# design.net
KiCad netlist of a schematic drawn in Altium Designer
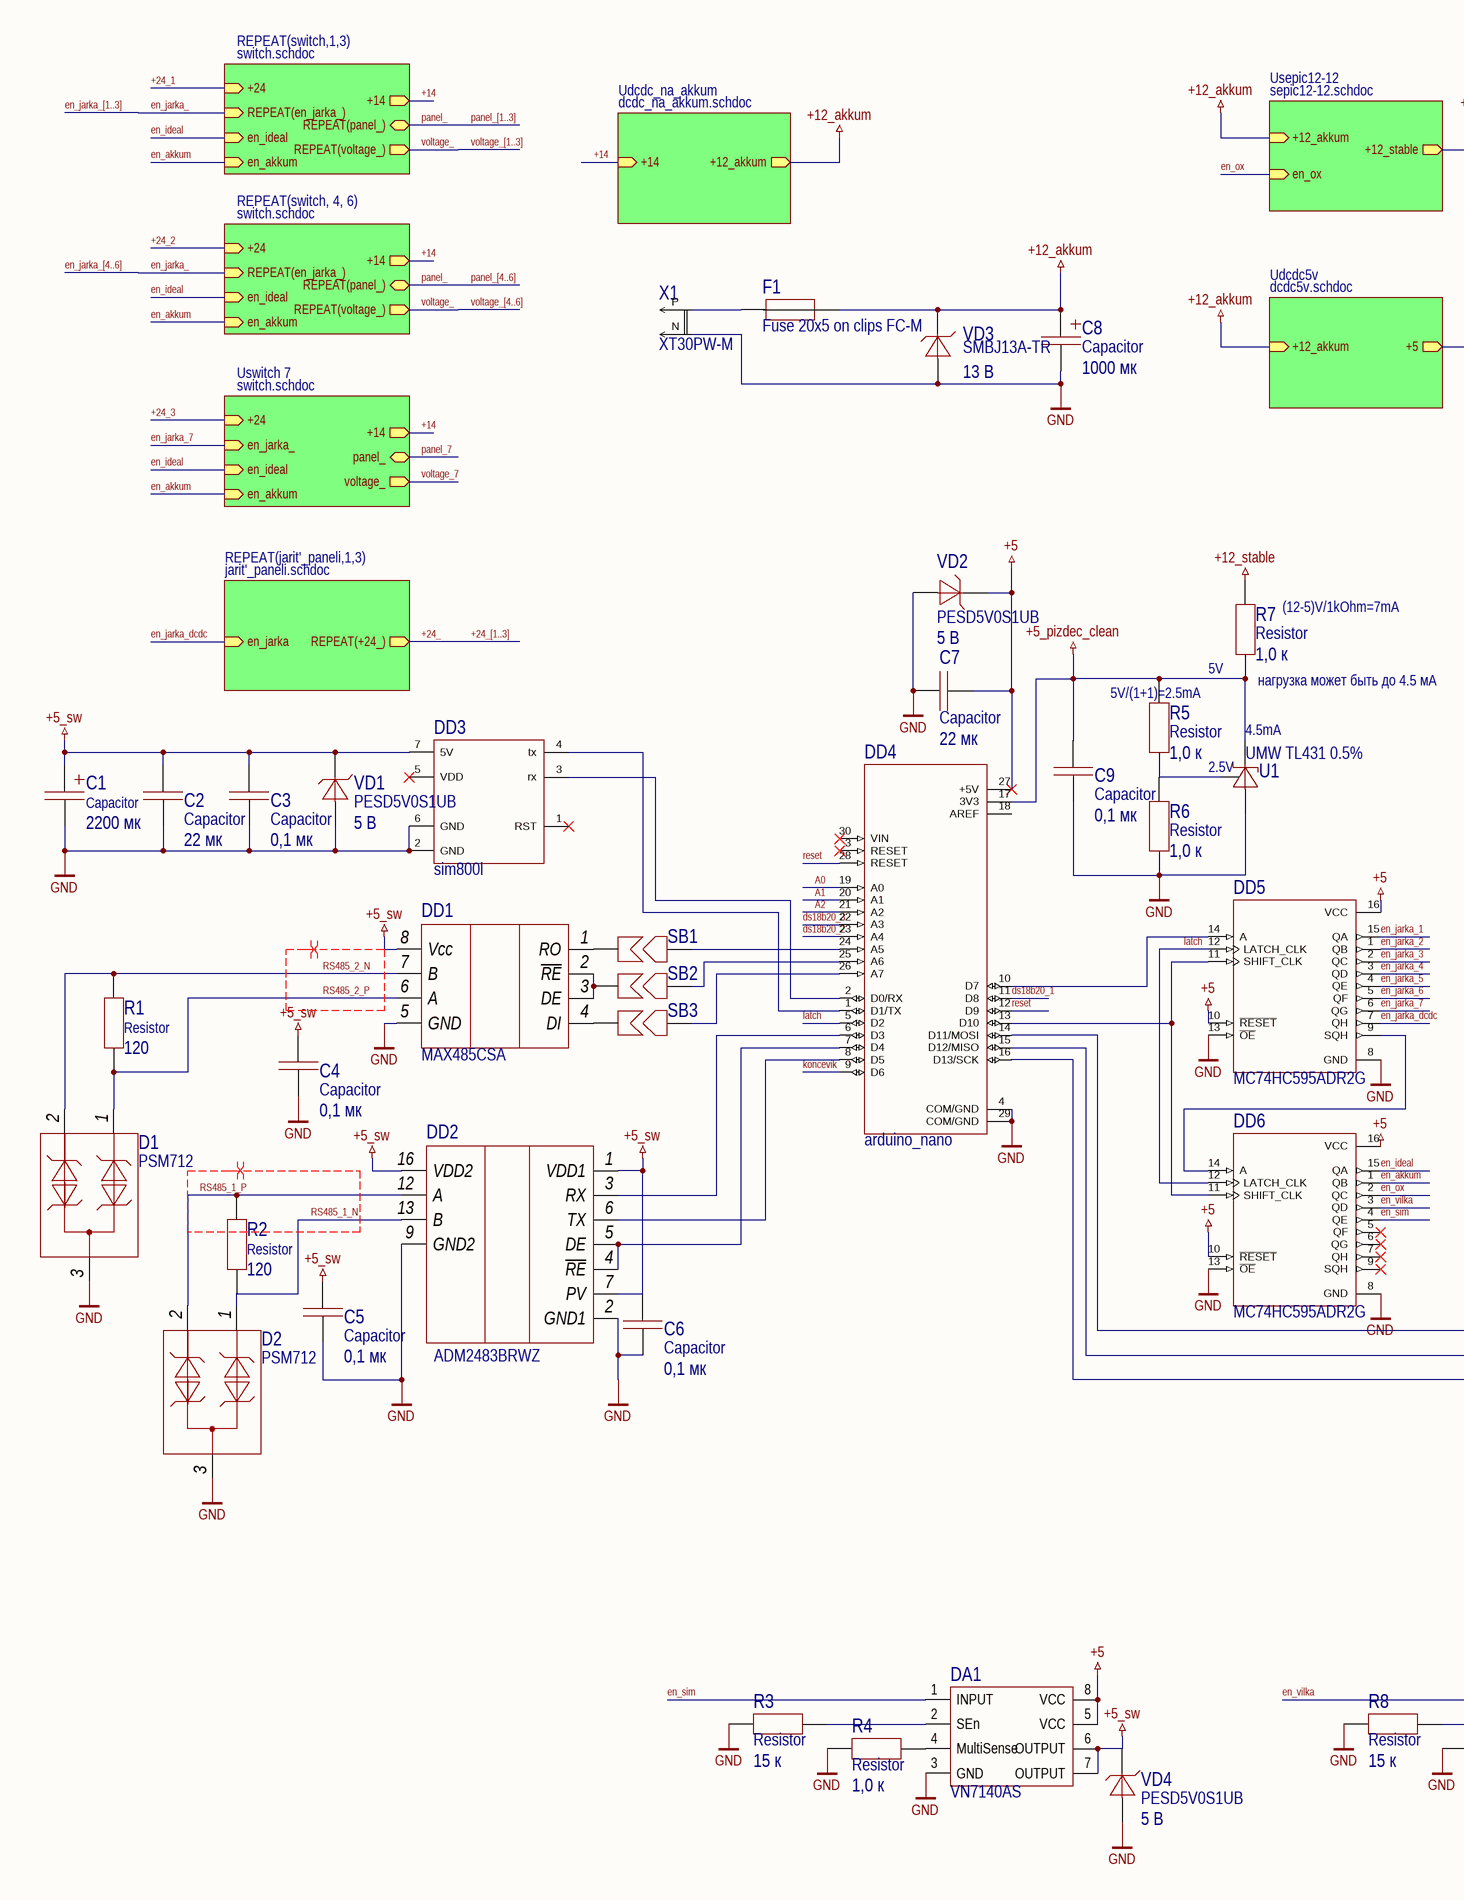
[diagram p0: хехема.SchDoc, left]
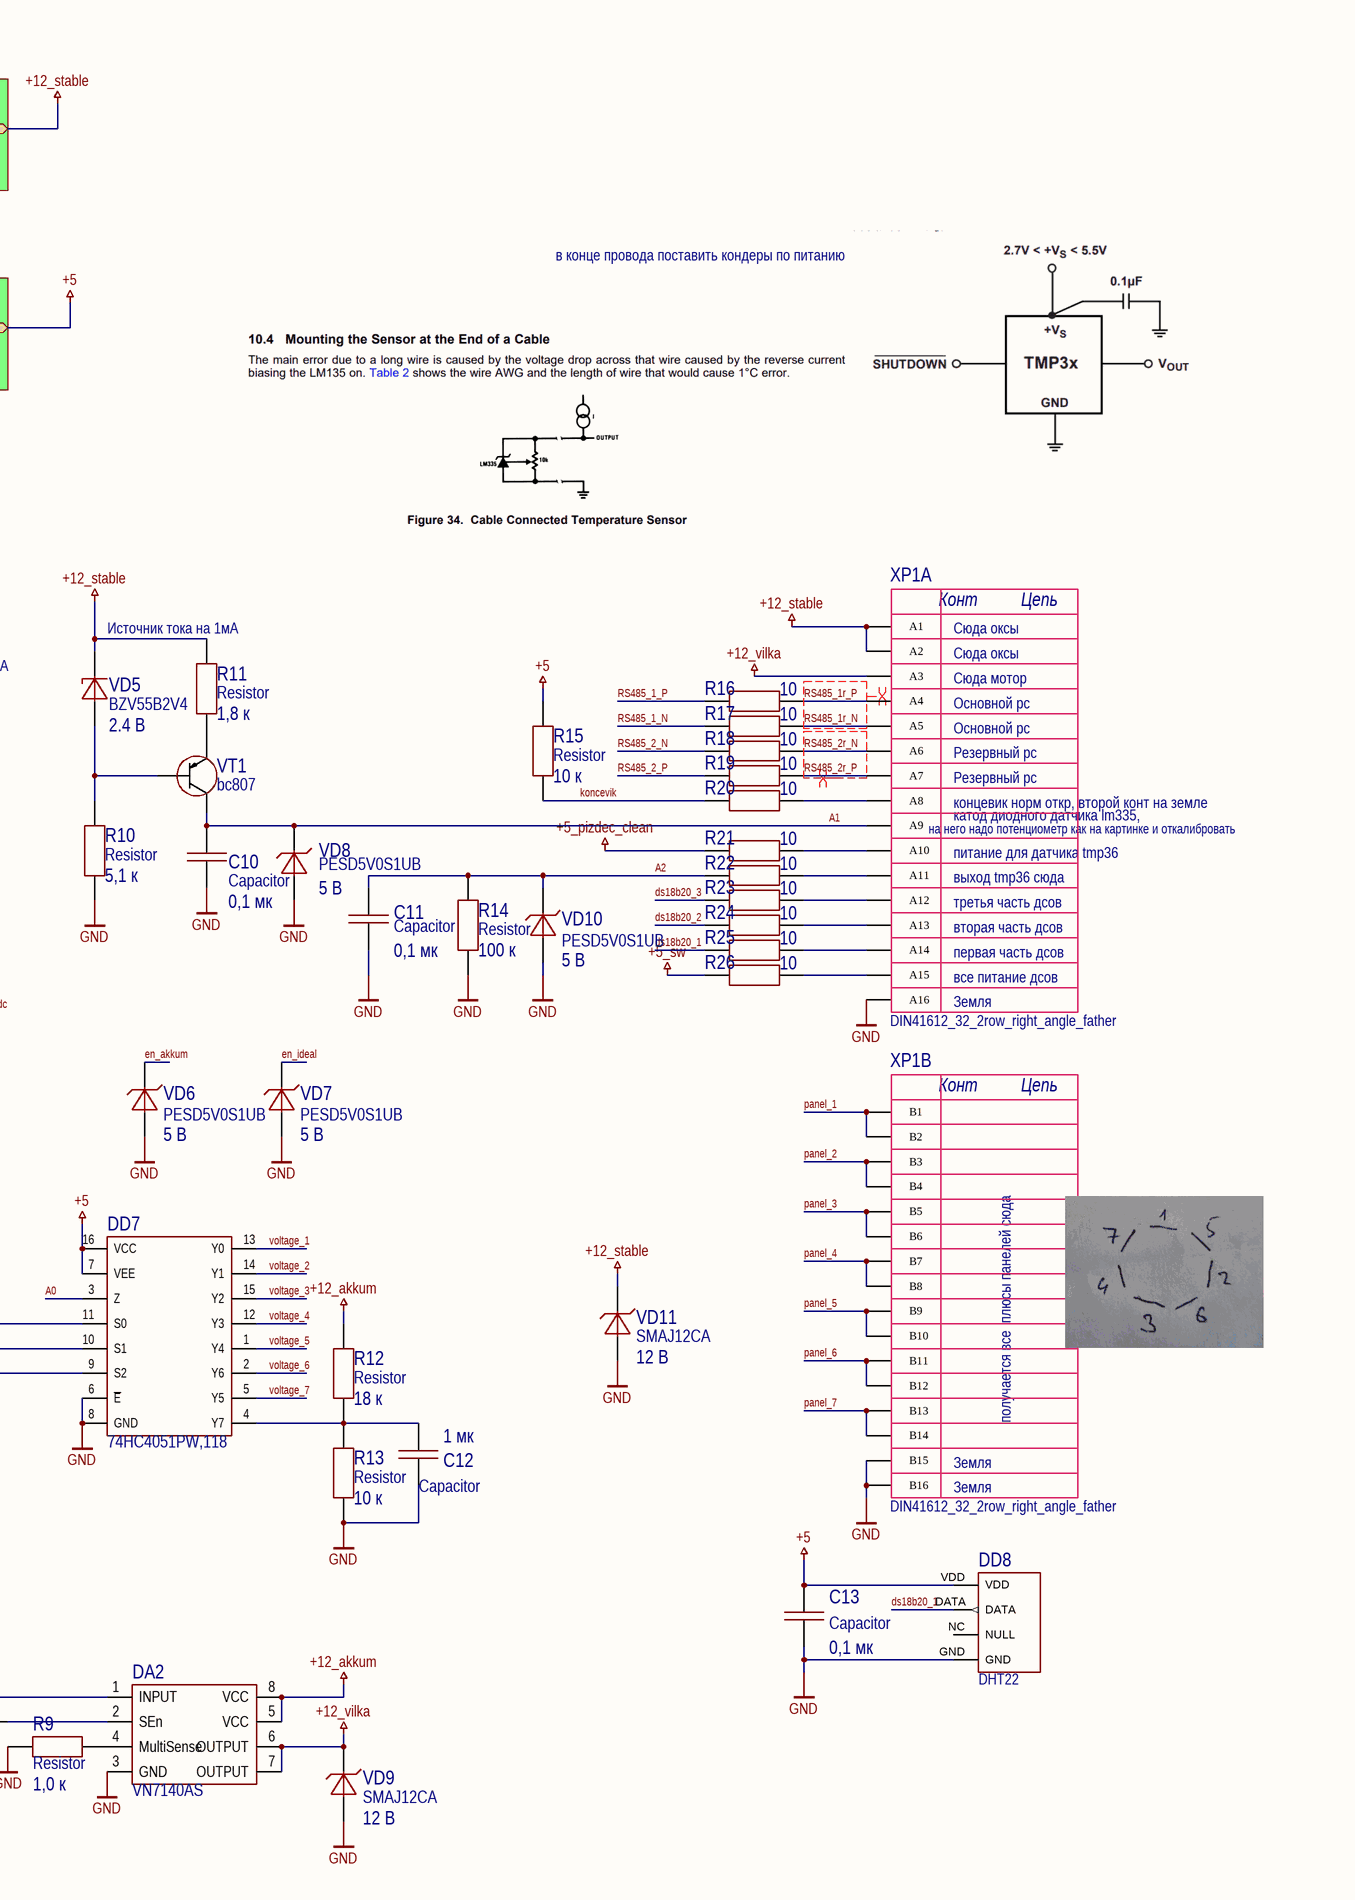
[diagram p1: хехема.SchDoc, right]

(export (version "E")
  (design (tool "Eeschema 10.0.6"))
  (components
    (comp (ref "C1")
      (value "Capacitor")
      (footprint "10x20_radial")
      (description "Конденсатор радиальный 2200мкФ 10В ±20% 10*19")
      (fields
        (field (name "ALTIUM_VALUE") "2200 мк")
        (field (name "PART NUMBER") "Capacitor_2200u_10V_10x20")
        (field (name "TOLERANCE") "20")
      )
      (libsource (lib "Hydrolib") (part "Capacitor_polar"))
    )
    (comp (ref "C2")
      (value "Capacitor")
      (footprint "1210C")
      (description "Конденсатор")
      (fields
        (field (name "ALTIUM_VALUE") "22 мк")
        (field (name "PART NUMBER") "Capacitor_22u_10_25V_X7R_1210C")
        (field (name "TOLERANCE") "0,1")
      )
      (libsource (lib "Hydrolib") (part "Capacitor"))
    )
    (comp (ref "C3")
      (value "Capacitor")
      (footprint "0603C")
      (description "Конденсатор")
      (fields
        (field (name "ALTIUM_VALUE") "0,1 мк")
        (field (name "PART NUMBER") "Capacitor_0,1u_10_50V_X7R_0603C")
        (field (name "TOLERANCE") "0,1")
      )
      (libsource (lib "Hydrolib") (part "Capacitor"))
    )
    (comp (ref "C4")
      (value "Capacitor")
      (footprint "0603C")
      (description "Конденсатор")
      (fields
        (field (name "ALTIUM_VALUE") "0,1 мк")
        (field (name "PART NUMBER") "Capacitor_0,1u_10_50V_X7R_0603C")
        (field (name "TOLERANCE") "0,1")
      )
      (libsource (lib "Hydrolib") (part "Capacitor"))
    )
    (comp (ref "C5")
      (value "Capacitor")
      (footprint "0603C")
      (description "Конденсатор")
      (fields
        (field (name "ALTIUM_VALUE") "0,1 мк")
        (field (name "PART NUMBER") "Capacitor_0,1u_10_50V_X7R_0603C")
        (field (name "TOLERANCE") "0,1")
      )
      (libsource (lib "Hydrolib") (part "Capacitor"))
    )
    (comp (ref "C6")
      (value "Capacitor")
      (footprint "0603C")
      (description "Конденсатор")
      (fields
        (field (name "ALTIUM_VALUE") "0,1 мк")
        (field (name "PART NUMBER") "Capacitor_0,1u_10_50V_X7R_0603C")
        (field (name "TOLERANCE") "0,1")
      )
      (libsource (lib "Hydrolib") (part "Capacitor"))
    )
    (comp (ref "C7")
      (value "Capacitor")
      (footprint "1210C")
      (description "Конденсатор")
      (fields
        (field (name "ALTIUM_VALUE") "22 мк")
        (field (name "PART NUMBER") "Capacitor_22u_10_25V_X7R_1210C")
        (field (name "TOLERANCE") "0,1")
      )
      (libsource (lib "Hydrolib") (part "Capacitor"))
    )
    (comp (ref "C8")
      (value "Capacitor")
      (footprint "SMD_cap_12,5x13,5")
      (description "Конденсатор алюминиевый электролитический 1000мкФ 25В 20% Low ESR 1100мА SMD12.5x13.5мм")
      (fields
        (field (name "ALTIUM_VALUE") "1000 мк")
        (field (name "PART NUMBER") "EEVFK1E102Q")
        (field (name "TOLERANCE") "20")
      )
      (libsource (lib "Hydrolib") (part "Capacitor_polar"))
    )
    (comp (ref "C9")
      (value "Capacitor")
      (footprint "0603C")
      (description "Конденсатор")
      (fields
        (field (name "ALTIUM_VALUE") "0,1 мк")
        (field (name "PART NUMBER") "Capacitor_0,1u_10_50V_X7R_0603C")
        (field (name "TOLERANCE") "0,1")
      )
      (libsource (lib "Hydrolib") (part "Capacitor"))
    )
    (comp (ref "C10")
      (value "Capacitor")
      (footprint "0603C")
      (description "Конденсатор")
      (fields
        (field (name "ALTIUM_VALUE") "0,1 мк")
        (field (name "PART NUMBER") "Capacitor_0,1u_10_50V_X7R_0603C")
        (field (name "TOLERANCE") "0,1")
      )
      (libsource (lib "Hydrolib") (part "Capacitor"))
    )
    (comp (ref "C11")
      (value "Capacitor")
      (footprint "0603C")
      (description "Конденсатор")
      (fields
        (field (name "ALTIUM_VALUE") "0,1 мк")
        (field (name "PART NUMBER") "Capacitor_0,1u_10_50V_X7R_0603C")
        (field (name "TOLERANCE") "0,1")
      )
      (libsource (lib "Hydrolib") (part "Capacitor"))
    )
    (comp (ref "C12")
      (value "Capacitor")
      (footprint "0603C")
      (description "Конденсатор")
      (fields
        (field (name "ALTIUM_VALUE") "1 мк")
        (field (name "PART NUMBER") "Capacitor_1u_10_50V_X7R_0603C")
        (field (name "TOLERANCE") "0,1")
      )
      (libsource (lib "Hydrolib") (part "Capacitor"))
    )
    (comp (ref "C13")
      (value "Capacitor")
      (footprint "0603C")
      (description "Конденсатор")
      (fields
        (field (name "ALTIUM_VALUE") "0,1 мк")
        (field (name "PART NUMBER") "Capacitor_0,1u_10_50V_X7R_0603C")
        (field (name "TOLERANCE") "0,1")
      )
      (libsource (lib "Hydrolib") (part "Capacitor"))
    )
    (comp (ref "D1")
      (value "PSM712")
      (footprint "SOT23-3")
      (description "Защитный диод для линии RS-485")
      (libsource (lib "Hydrolib") (part "TVS_2_2dir"))
    )
    (comp (ref "D2")
      (value "PSM712")
      (footprint "SOT23-3")
      (description "Защитный диод для линии RS-485")
      (libsource (lib "Hydrolib") (part "TVS_2_2dir"))
    )
    (comp (ref "DA1")
      (value "VN7140AS")
      (footprint "SOP8")
      (description "Силовой ключ верхнего плеча с аналоговой обратной связью MultiSense автомобильного применения")
      (libsource (lib "Hydrolib") (part "VN7140AS"))
    )
    (comp (ref "DA2")
      (value "VN7140AS")
      (footprint "SOP8")
      (description "Силовой ключ верхнего плеча с аналоговой обратной связью MultiSense автомобильного применения")
      (libsource (lib "Hydrolib") (part "VN7140AS"))
    )
    (comp (ref "DD1")
      (value "MAX485CSA")
      (footprint "SOIC-8")
      (description "RS-485 приёмопередатчик")
      (libsource (lib "Hydrolib") (part "MAX485CSA"))
    )
    (comp (ref "DD2")
      (value "ADM2483BRWZ")
      (footprint "SOIC-16W")
      (description "Прием передатчик RS485 с гальванической развязкой")
      (libsource (lib "Hydrolib") (part "ADM2483BRWZ"))
    )
    (comp (ref "DD3") (value "sim800l") (footprint "sim800l") (libsource (lib "Hydrolib") (part "sim800l")))
    (comp (ref "DD4")
      (value "arduino_nano")
      (footprint "arduino_nano")
      (description "ардуинка на стойках")
      (fields (field (name "MP") "Arduino Nano") (field (name "MF") "Arduino"))
      (libsource (lib "Hydrolib") (part "ARDUINO_NANO"))
    )
    (comp (ref "DD5")
      (value "MC74HC595ADR2G")
      (footprint "SOIC-16")
      (description "8-ми битный сдвиговый регистр")
      (libsource (lib "Hydrolib") (part "MC74HC595ADR2G"))
    )
    (comp (ref "DD6")
      (value "MC74HC595ADR2G")
      (footprint "SOIC-16")
      (description "8-ми битный сдвиговый регистр")
      (libsource (lib "Hydrolib") (part "MC74HC595ADR2G"))
    )
    (comp (ref "DD7")
      (value "74HC4051PW,118")
      (footprint "TSSOP-16")
      (description "Мультиплексор аналоговый 8 в 1 КМОП кристалл, TSSOP16")
      (libsource (lib "Hydrolib") (part "74HC4051PW,118"))
    )
    (comp (ref "DD8")
      (value "DHT22")
      (footprint "DHT22")
      (description "Датчик температуры и влажности на базе AM2302")
      (libsource (lib "Hydrolib") (part "DHT22"))
    )
    (comp (ref "F1")
      (value "Fuse 20x5 on clips FC-M")
      (footprint "fuse_20x5_on_clips_FC-M")
      (description "Предохранитель 20*5 на креплениях")
      (libsource (lib "Hydrolib") (part "Fuse"))
    )
    (comp (ref "R1")
      (value "Resistor")
      (footprint "1206R")
      (description "Резистор номиналом 120 Ом и точностью 1%")
      (fields
        (field (name "ALTIUM_VALUE") "120")
        (field (name "PART NUMBER") "Resistor_120_1_0603")
        (field (name "TOLERANCE") "1%")
      )
      (libsource (lib "Hydrolib") (part "Resistor"))
    )
    (comp (ref "R2")
      (value "Resistor")
      (footprint "1206R")
      (description "Резистор номиналом 120 Ом и точностью 1%")
      (fields
        (field (name "ALTIUM_VALUE") "120")
        (field (name "PART NUMBER") "Resistor_120_1_0603")
        (field (name "TOLERANCE") "1%")
      )
      (libsource (lib "Hydrolib") (part "Resistor"))
    )
    (comp (ref "R3")
      (value "Resistor")
      (footprint "0603R")
      (description "Резистор номиналом 15 кОм и точностью 1%")
      (fields
        (field (name "ALTIUM_VALUE") "15 к")
        (field (name "PART NUMBER") "Resistor_15k_1_0603")
        (field (name "TOLERANCE") "1%")
      )
      (libsource (lib "") (part "Resistor_1"))
    )
    (comp (ref "R4")
      (value "Resistor")
      (footprint "0603R")
      (description "Резистор номиналом 1,0 кОм и точностью 1%")
      (fields
        (field (name "ALTIUM_VALUE") "1,0 к")
        (field (name "PART NUMBER") "Resistor_1.0k_1_0603")
        (field (name "TOLERANCE") "1%")
      )
      (libsource (lib "") (part "Resistor_1"))
    )
    (comp (ref "R5")
      (value "Resistor")
      (footprint "0603R")
      (description "Резистор номиналом 1,0 кОм и точностью 1%")
      (fields
        (field (name "ALTIUM_VALUE") "1,0 к")
        (field (name "PART NUMBER") "Resistor_1.0k_1_0603")
        (field (name "TOLERANCE") "1%")
      )
      (libsource (lib "Hydrolib") (part "Resistor"))
    )
    (comp (ref "R6")
      (value "Resistor")
      (footprint "0603R")
      (description "Резистор номиналом 1,0 кОм и точностью 1%")
      (fields
        (field (name "ALTIUM_VALUE") "1,0 к")
        (field (name "PART NUMBER") "Resistor_1.0k_1_0603")
        (field (name "TOLERANCE") "1%")
      )
      (libsource (lib "Hydrolib") (part "Resistor"))
    )
    (comp (ref "R7")
      (value "Resistor")
      (footprint "0603R")
      (description "Резистор номиналом 1,0 кОм и точностью 1%")
      (fields
        (field (name "ALTIUM_VALUE") "1,0 к")
        (field (name "PART NUMBER") "Resistor_1.0k_1_0603")
        (field (name "TOLERANCE") "1%")
      )
      (libsource (lib "Hydrolib") (part "Resistor"))
    )
    (comp (ref "R8")
      (value "Resistor")
      (footprint "0603R")
      (description "Резистор номиналом 15 кОм и точностью 1%")
      (fields
        (field (name "ALTIUM_VALUE") "15 к")
        (field (name "PART NUMBER") "Resistor_15k_1_0603")
        (field (name "TOLERANCE") "1%")
      )
      (libsource (lib "") (part "Resistor_1"))
    )
    (comp (ref "R9")
      (value "Resistor")
      (footprint "0603R")
      (description "Резистор номиналом 1,0 кОм и точностью 1%")
      (fields
        (field (name "ALTIUM_VALUE") "1,0 к")
        (field (name "PART NUMBER") "Resistor_1.0k_1_0603")
        (field (name "TOLERANCE") "1%")
      )
      (libsource (lib "") (part "Resistor_1"))
    )
    (comp (ref "R10")
      (value "Resistor")
      (footprint "0603R")
      (description "Резистор номиналом 5,1 кОм и точностью 1%")
      (fields
        (field (name "ALTIUM_VALUE") "5,1 к")
        (field (name "PART NUMBER") "Resistor_5.1k_1_0603")
        (field (name "TOLERANCE") "1%")
      )
      (libsource (lib "Hydrolib") (part "Resistor"))
    )
    (comp (ref "R11")
      (value "Resistor")
      (footprint "0603R")
      (description "Резистор номиналом 1,8 кОм и точностью 1%")
      (fields
        (field (name "ALTIUM_VALUE") "1,8 к")
        (field (name "PART NUMBER") "Resistor_1.8k_1_0603")
        (field (name "TOLERANCE") "1%")
      )
      (libsource (lib "Hydrolib") (part "Resistor"))
    )
    (comp (ref "R12")
      (value "Resistor")
      (footprint "0603R")
      (description "Резистор номиналом 18 кОм и точностью 1%")
      (fields
        (field (name "ALTIUM_VALUE") "18 к")
        (field (name "PART NUMBER") "Resistor_18k_1_0603")
        (field (name "TOLERANCE") "1%")
      )
      (libsource (lib "Hydrolib") (part "Resistor"))
    )
    (comp (ref "R13")
      (value "Resistor")
      (footprint "0603R")
      (description "Резистор номиналом 10 кОм и точностью 1%")
      (fields
        (field (name "ALTIUM_VALUE") "10 к")
        (field (name "PART NUMBER") "Resistor_10k_1_0603")
        (field (name "TOLERANCE") "1%")
      )
      (libsource (lib "Hydrolib") (part "Resistor"))
    )
    (comp (ref "R14")
      (value "Resistor")
      (footprint "0603R")
      (description "Резистор номиналом 100 кОм и точностью 1%")
      (fields
        (field (name "ALTIUM_VALUE") "100 к")
        (field (name "PART NUMBER") "Resistor_100k_1_0603")
        (field (name "TOLERANCE") "1%")
      )
      (libsource (lib "Hydrolib") (part "Resistor"))
    )
    (comp (ref "R15")
      (value "Resistor")
      (footprint "0603R")
      (description "Резистор номиналом 10 кОм и точностью 1%")
      (fields
        (field (name "ALTIUM_VALUE") "10 к")
        (field (name "PART NUMBER") "Resistor_10k_1_0603")
        (field (name "TOLERANCE") "1%")
      )
      (libsource (lib "Hydrolib") (part "Resistor"))
    )
    (comp (ref "R16")
      (value "10")
      (footprint "0603R")
      (description "Резистор номиналом 10 Ом и точностью 1%")
      (fields (field (name "PART NUMBER") "Resistor_10_1_0603") (field (name "TOLERANCE") "1%"))
      (libsource (lib "") (part "Resistor_1"))
    )
    (comp (ref "R17")
      (value "10")
      (footprint "0603R")
      (description "Резистор номиналом 10 Ом и точностью 1%")
      (fields (field (name "PART NUMBER") "Resistor_10_1_0603") (field (name "TOLERANCE") "1%"))
      (libsource (lib "") (part "Resistor_1"))
    )
    (comp (ref "R18")
      (value "10")
      (footprint "0603R")
      (description "Резистор номиналом 10 Ом и точностью 1%")
      (fields (field (name "PART NUMBER") "Resistor_10_1_0603") (field (name "TOLERANCE") "1%"))
      (libsource (lib "") (part "Resistor_1"))
    )
    (comp (ref "R19")
      (value "10")
      (footprint "0603R")
      (description "Резистор номиналом 10 Ом и точностью 1%")
      (fields (field (name "PART NUMBER") "Resistor_10_1_0603") (field (name "TOLERANCE") "1%"))
      (libsource (lib "") (part "Resistor_1"))
    )
    (comp (ref "R20")
      (value "10")
      (footprint "0603R")
      (description "Резистор номиналом 10 Ом и точностью 1%")
      (fields (field (name "PART NUMBER") "Resistor_10_1_0603") (field (name "TOLERANCE") "1%"))
      (libsource (lib "") (part "Resistor_1"))
    )
    (comp (ref "R21")
      (value "10")
      (footprint "0603R")
      (description "Резистор номиналом 10 Ом и точностью 1%")
      (fields (field (name "PART NUMBER") "Resistor_10_1_0603") (field (name "TOLERANCE") "1%"))
      (libsource (lib "") (part "Resistor_1"))
    )
    (comp (ref "R22")
      (value "10")
      (footprint "0603R")
      (description "Резистор номиналом 10 Ом и точностью 1%")
      (fields (field (name "PART NUMBER") "Resistor_10_1_0603") (field (name "TOLERANCE") "1%"))
      (libsource (lib "") (part "Resistor_1"))
    )
    (comp (ref "R23")
      (value "10")
      (footprint "0603R")
      (description "Резистор номиналом 10 Ом и точностью 1%")
      (fields (field (name "PART NUMBER") "Resistor_10_1_0603") (field (name "TOLERANCE") "1%"))
      (libsource (lib "") (part "Resistor_1"))
    )
    (comp (ref "R24")
      (value "10")
      (footprint "0603R")
      (description "Резистор номиналом 10 Ом и точностью 1%")
      (fields (field (name "PART NUMBER") "Resistor_10_1_0603") (field (name "TOLERANCE") "1%"))
      (libsource (lib "") (part "Resistor_1"))
    )
    (comp (ref "R25")
      (value "10")
      (footprint "0603R")
      (description "Резистор номиналом 10 Ом и точностью 1%")
      (fields (field (name "PART NUMBER") "Resistor_10_1_0603") (field (name "TOLERANCE") "1%"))
      (libsource (lib "") (part "Resistor_1"))
    )
    (comp (ref "R26")
      (value "10")
      (footprint "0603R")
      (description "Резистор номиналом 10 Ом и точностью 1%")
      (fields (field (name "PART NUMBER") "Resistor_10_1_0603") (field (name "TOLERANCE") "1%"))
      (libsource (lib "") (part "Resistor_1"))
    )
    (comp (ref "SB1")
      (value "SB")
      (footprint "0805SB")
      (description "Solder bridge, мост припоя, запаиваемая перемычка, net tie, jumper")
      (libsource (lib "Hydrolib") (part "SB"))
    )
    (comp (ref "SB2")
      (value "SB")
      (footprint "0805SB")
      (description "Solder bridge, мост припоя, запаиваемая перемычка, net tie, jumper")
      (libsource (lib "Hydrolib") (part "SB"))
    )
    (comp (ref "SB3")
      (value "SB")
      (footprint "0805SB")
      (description "Solder bridge, мост припоя, запаиваемая перемычка, net tie, jumper")
      (libsource (lib "Hydrolib") (part "SB"))
    )
    (comp (ref "U1")
      (value "UMW TL431 0.5%")
      (footprint "SOT23-3")
      (description "Источник опорного напряжения , программируемый стабилитрон [SOT-23-3]")
      (libsource (lib "Hydrolib") (part "precision_shunt_regulator"))
    )
    (comp (ref "VD1")
      (value "PESD5V0S1UB")
      (footprint "SOD523")
      (description "Защитный диод на 5 В, рассеиваемая мощность 330 Вт")
      (fields (field (name "ALTIUM_VALUE") "5 В"))
      (libsource (lib "Hydrolib") (part "TVS_1_1dir"))
    )
    (comp (ref "VD2")
      (value "PESD5V0S1UB")
      (footprint "SOD523")
      (description "Защитный диод на 5 В, рассеиваемая мощность 330 Вт")
      (fields (field (name "ALTIUM_VALUE") "5 В"))
      (libsource (lib "Hydrolib") (part "TVS_1_1dir"))
    )
    (comp (ref "VD3")
      (value "SMBJ13A-TR")
      (footprint "SMB")
      (description "Защитный диод на 13 В, рассеиваемая мощность 600 Вт")
      (fields (field (name "ALTIUM_VALUE") "13 В"))
      (libsource (lib "Hydrolib") (part "TVS_1_1dir"))
    )
    (comp (ref "VD4")
      (value "PESD5V0S1UB")
      (footprint "SOD523")
      (description "Защитный диод на 5 В, рассеиваемая мощность 330 Вт")
      (fields (field (name "ALTIUM_VALUE") "5 В"))
      (libsource (lib "Hydrolib") (part "TVS_1_1dir"))
    )
    (comp (ref "VD5")
      (value "BZV55B2V4")
      (footprint "mini_MELF_3.5mm")
      (description "Стабилитрон на 2.4 В, рассеиваемая мощность 0.5 Вт")
      (fields (field (name "ALTIUM_VALUE") "2.4 В"))
      (libsource (lib "Hydrolib") (part "Zener"))
    )
    (comp (ref "VD6")
      (value "PESD5V0S1UB")
      (footprint "SOD523")
      (description "Защитный диод на 5 В, рассеиваемая мощность 330 Вт")
      (fields (field (name "ALTIUM_VALUE") "5 В"))
      (libsource (lib "Hydrolib") (part "TVS_1_1dir"))
    )
    (comp (ref "VD7")
      (value "PESD5V0S1UB")
      (footprint "SOD523")
      (description "Защитный диод на 5 В, рассеиваемая мощность 330 Вт")
      (fields (field (name "ALTIUM_VALUE") "5 В"))
      (libsource (lib "Hydrolib") (part "TVS_1_1dir"))
    )
    (comp (ref "VD8")
      (value "PESD5V0S1UB")
      (footprint "SOD523")
      (description "Защитный диод на 5 В, рассеиваемая мощность 330 Вт")
      (fields (field (name "ALTIUM_VALUE") "5 В"))
      (libsource (lib "Hydrolib") (part "TVS_1_1dir"))
    )
    (comp (ref "VD9")
      (value "SMAJ12CA")
      (footprint "SMA")
      (description "Защитный диод на 12 В, рассеиваемая мощность 400 Вт")
      (fields (field (name "ALTIUM_VALUE") "12 В"))
      (libsource (lib "Hydrolib") (part "TVS_1_1dir"))
    )
    (comp (ref "VD10")
      (value "PESD5V0S1UB")
      (footprint "SOD523")
      (description "Защитный диод на 5 В, рассеиваемая мощность 330 Вт")
      (fields (field (name "ALTIUM_VALUE") "5 В"))
      (libsource (lib "Hydrolib") (part "TVS_1_1dir"))
    )
    (comp (ref "VD11")
      (value "SMAJ12CA")
      (footprint "SMA")
      (description "Защитный диод на 12 В, рассеиваемая мощность 400 Вт")
      (fields (field (name "ALTIUM_VALUE") "12 В"))
      (libsource (lib "Hydrolib") (part "TVS_1_1dir"))
    )
    (comp (ref "VT1")
      (value "bc807")
      (footprint "SOT23-3")
      (description "Биполярный транзистор PNP 45В 0.5А 0.31Вт")
      (libsource (lib "Hydrolib") (part "pnp"))
    )
    (comp (ref "X1")
      (value "XT30PW-M")
      (footprint "XT30PW-M")
      (description "30 А (15 продолжительно), 2 контакта разъем угловой отец")
      (libsource (lib "Hydrolib") (part "Polar_Conn"))
    )
    (comp (ref "XP1")
      (value "DIN41612_32_2row_right_angle_father")
      (footprint "DIN41612_32_2row_right_angle_father")
      (libsource (lib "Hydrolib") (part "DIN41612_32_2row"))
    )
  )
  (nets
    (net (code "1") (name "+5") (class "Default")
      (node (ref "C13") (pin "2") (pinfunction "2_2") (pintype "passive"))
      (node (ref "C7") (pin "1") (pinfunction "1_1") (pintype "passive"))
      (node (ref "DA1") (pin "5") (pinfunction "VCC_5") (pintype "passive"))
      (node (ref "DA1") (pin "8") (pinfunction "VCC_8") (pintype "passive"))
      (node (ref "DD4") (pin "27") (pinfunction "+5V_27") (pintype "power_in"))
      (node (ref "DD5") (pin "10") (pinfunction "~{RESET}_10") (pintype "input"))
      (node (ref "DD5") (pin "16") (pinfunction "VCC_16") (pintype "power_in"))
      (node (ref "DD6") (pin "10") (pinfunction "~{RESET}_10") (pintype "input"))
      (node (ref "DD6") (pin "16") (pinfunction "VCC_16") (pintype "power_in"))
      (node (ref "DD7") (pin "16") (pinfunction "VCC_16") (pintype "passive"))
      (node (ref "DD7") (pin "7") (pinfunction "VEE_7") (pintype "passive"))
      (node (ref "DD8") (pin "VDD") (pinfunction "VDD_VDD") (pintype "power_in"))
      (node (ref "R15") (pin "2") (pinfunction "2_2") (pintype "passive"))
      (node (ref "VD2") (pin "2") (pinfunction "2_2") (pintype "passive"))
    )
    (net (code "2") (name "+5_pizdec_clean") (class "Default")
      (node (ref "C9") (pin "2") (pinfunction "2_2") (pintype "passive"))
      (node (ref "DD4") (pin "17") (pinfunction "3V3_17") (pintype "power_in"))
      (node (ref "R21") (pin "1") (pinfunction "1_1") (pintype "passive"))
      (node (ref "R5") (pin "2") (pinfunction "2_2") (pintype "passive"))
      (node (ref "R7") (pin "1") (pinfunction "1_1") (pintype "passive"))
      (node (ref "U1") (pin "2") (pinfunction "2_2") (pintype "passive"))
    )
    (net (code "3") (name "+5_sw") (class "Default")
      (node (ref "C1") (pin "1") (pinfunction "1_1") (pintype "passive"))
      (node (ref "C2") (pin "2") (pinfunction "2_2") (pintype "passive"))
      (node (ref "C3") (pin "2") (pinfunction "2_2") (pintype "passive"))
      (node (ref "C4") (pin "1") (pinfunction "1_1") (pintype "passive"))
      (node (ref "C5") (pin "2") (pinfunction "2_2") (pintype "passive"))
      (node (ref "C6") (pin "2") (pinfunction "2_2") (pintype "passive"))
      (node (ref "DA1") (pin "6") (pinfunction "OUTPUT_6") (pintype "passive"))
      (node (ref "DA1") (pin "7") (pinfunction "OUTPUT_7") (pintype "passive"))
      (node (ref "DD1") (pin "8") (pinfunction "Vcc_8") (pintype "passive"))
      (node (ref "DD2") (pin "1") (pinfunction "VDD1_1") (pintype "passive"))
      (node (ref "DD2") (pin "16") (pinfunction "VDD2_16") (pintype "passive"))
      (node (ref "DD2") (pin "7") (pinfunction "PV_7") (pintype "passive"))
      (node (ref "DD3") (pin "7") (pinfunction "5V_7") (pintype "passive"))
      (node (ref "R26") (pin "1") (pinfunction "1_1") (pintype "passive"))
      (node (ref "VD1") (pin "2") (pinfunction "2_2") (pintype "passive"))
      (node (ref "VD4") (pin "2") (pinfunction "2_2") (pintype "passive"))
    )
    (net (code "4") (name "+12_akkum") (class "Default")
      (node (ref "C8") (pin "1") (pinfunction "1_1") (pintype "passive"))
      (node (ref "DA2") (pin "5") (pinfunction "VCC_5") (pintype "passive"))
      (node (ref "DA2") (pin "8") (pinfunction "VCC_8") (pintype "passive"))
      (node (ref "F1") (pin "2") (pinfunction "2_2") (pintype "passive"))
      (node (ref "R12") (pin "2") (pinfunction "2_2") (pintype "passive"))
      (node (ref "VD3") (pin "2") (pinfunction "2_2") (pintype "passive"))
    )
    (net (code "5") (name "+12_stable") (class "Default")
      (node (ref "R11") (pin "2") (pinfunction "2_2") (pintype "passive"))
      (node (ref "R7") (pin "2") (pinfunction "2_2") (pintype "passive"))
      (node (ref "VD11") (pin "2") (pinfunction "2_2") (pintype "passive"))
      (node (ref "VD5") (pin "2") (pinfunction "2_2") (pintype "passive"))
      (node (ref "XP1") (pin "A1") (pinfunction "A1_A1") (pintype "passive"))
      (node (ref "XP1") (pin "A2") (pinfunction "A2_A2") (pintype "passive"))
    )
    (net (code "6") (name "+12_vilka") (class "Default")
      (node (ref "DA2") (pin "6") (pinfunction "OUTPUT_6") (pintype "passive"))
      (node (ref "DA2") (pin "7") (pinfunction "OUTPUT_7") (pintype "passive"))
      (node (ref "VD9") (pin "2") (pinfunction "2_2") (pintype "passive"))
      (node (ref "XP1") (pin "A3") (pinfunction "A3_A3") (pintype "passive"))
    )
    (net (code "13") (name "/A0") (class "Default")
      (node (ref "DD4") (pin "19") (pinfunction "A0_19") (pintype "input"))
      (node (ref "DD7") (pin "3") (pinfunction "Z_3") (pintype "passive"))
    )
    (net (code "14") (name "/A1") (class "Default")
      (node (ref "C10") (pin "2") (pinfunction "2_2") (pintype "passive"))
      (node (ref "DD4") (pin "20") (pinfunction "A1_20") (pintype "input"))
      (node (ref "VD8") (pin "2") (pinfunction "2_2") (pintype "passive"))
      (node (ref "VT1") (pin "3") (pinfunction "3_3") (pintype "passive"))
      (node (ref "XP1") (pin "A9") (pinfunction "A9_A9") (pintype "passive"))
    )
    (net (code "15") (name "/A2") (class "Default")
      (node (ref "C11") (pin "2") (pinfunction "2_2") (pintype "passive"))
      (node (ref "DD4") (pin "21") (pinfunction "A2_21") (pintype "input"))
      (node (ref "R14") (pin "2") (pinfunction "2_2") (pintype "passive"))
      (node (ref "R22") (pin "1") (pinfunction "1_1") (pintype "passive"))
      (node (ref "VD10") (pin "2") (pinfunction "2_2") (pintype "passive"))
    )
    (net (code "16") (name "/RS485_1_N") (class "Default")
      (node (ref "D2") (pin "1") (pinfunction "14_1") (pintype "passive"))
      (node (ref "DD2") (pin "13") (pinfunction "B_13") (pintype "passive"))
      (node (ref "R17") (pin "1") (pinfunction "1_1") (pintype "passive"))
      (node (ref "R2") (pin "1") (pinfunction "1_1") (pintype "passive"))
    )
    (net (code "17") (name "/RS485_1_P") (class "Default")
      (node (ref "D2") (pin "2") (pinfunction "15_2") (pintype "passive"))
      (node (ref "DD2") (pin "12") (pinfunction "A_12") (pintype "passive"))
      (node (ref "R16") (pin "1") (pinfunction "1_1") (pintype "passive"))
      (node (ref "R2") (pin "2") (pinfunction "2_2") (pintype "passive"))
    )
    (net (code "18") (name "/RS485_1r_N") (class "Default")
      (node (ref "R17") (pin "2") (pinfunction "2_2") (pintype "passive"))
      (node (ref "XP1") (pin "A5") (pinfunction "A5_A5") (pintype "passive"))
    )
    (net (code "19") (name "/RS485_1r_P") (class "Default")
      (node (ref "R16") (pin "2") (pinfunction "2_2") (pintype "passive"))
      (node (ref "XP1") (pin "A4") (pinfunction "A4_A4") (pintype "passive"))
    )
    (net (code "20") (name "/RS485_2_N") (class "Default")
      (node (ref "D1") (pin "2") (pinfunction "15_2") (pintype "passive"))
      (node (ref "DD1") (pin "7") (pinfunction "B_7") (pintype "passive"))
      (node (ref "R1") (pin "2") (pinfunction "2_2") (pintype "passive"))
      (node (ref "R18") (pin "1") (pinfunction "1_1") (pintype "passive"))
    )
    (net (code "21") (name "/RS485_2_P") (class "Default")
      (node (ref "D1") (pin "1") (pinfunction "14_1") (pintype "passive"))
      (node (ref "DD1") (pin "6") (pinfunction "A_6") (pintype "passive"))
      (node (ref "R1") (pin "1") (pinfunction "1_1") (pintype "passive"))
      (node (ref "R19") (pin "1") (pinfunction "1_1") (pintype "passive"))
    )
    (net (code "22") (name "/RS485_2r_N") (class "Default")
      (node (ref "R18") (pin "2") (pinfunction "2_2") (pintype "passive"))
      (node (ref "XP1") (pin "A6") (pinfunction "A6_A6") (pintype "passive"))
    )
    (net (code "23") (name "/RS485_2r_P") (class "Default")
      (node (ref "R19") (pin "2") (pinfunction "2_2") (pintype "passive"))
      (node (ref "XP1") (pin "A7") (pinfunction "A7_A7") (pintype "passive"))
    )
    (net (code "24") (name "/ds18b20_1") (class "Default")
      (node (ref "DD4") (pin "11") (pinfunction "D8_11") (pintype "bidirectional"))
      (node (ref "DD8") (pin "DATA") (pinfunction "DATA_DATA") (pintype "output"))
      (node (ref "R25") (pin "1") (pinfunction "1_1") (pintype "passive"))
    )
    (net (code "25") (name "/ds18b20_2") (class "Default")
      (node (ref "DD4") (pin "23") (pinfunction "A4_23") (pintype "input"))
      (node (ref "R24") (pin "1") (pinfunction "1_1") (pintype "passive"))
    )
    (net (code "26") (name "/ds18b20_3") (class "Default")
      (node (ref "DD4") (pin "22") (pinfunction "A3_22") (pintype "input"))
      (node (ref "R23") (pin "1") (pinfunction "1_1") (pintype "passive"))
    )
    (net (code "27") (name "/en_akkum") (class "Default")
      (node (ref "DD6") (pin "1") (pinfunction "QB_1") (pintype "output"))
      (node (ref "VD6") (pin "2") (pinfunction "2_2") (pintype "passive"))
    )
    (net (code "28") (name "/en_ideal") (class "Default")
      (node (ref "DD6") (pin "15") (pinfunction "QA_15") (pintype "output"))
      (node (ref "VD7") (pin "2") (pinfunction "2_2") (pintype "passive"))
    )
    (net (code "30") (name "/en_jarka_1") (class "Default")
      (node (ref "DD5") (pin "15") (pinfunction "QA_15") (pintype "output"))
    )
    (net (code "31") (name "/en_jarka_2") (class "Default")
      (node (ref "DD5") (pin "1") (pinfunction "QB_1") (pintype "output"))
    )
    (net (code "32") (name "/en_jarka_3") (class "Default")
      (node (ref "DD5") (pin "2") (pinfunction "QC_2") (pintype "output"))
    )
    (net (code "33") (name "/en_jarka_4") (class "Default")
      (node (ref "DD5") (pin "3") (pinfunction "QD_3") (pintype "output"))
    )
    (net (code "34") (name "/en_jarka_5") (class "Default")
      (node (ref "DD5") (pin "4") (pinfunction "QE_4") (pintype "output"))
    )
    (net (code "35") (name "/en_jarka_6") (class "Default")
      (node (ref "DD5") (pin "5") (pinfunction "QF_5") (pintype "output"))
    )
    (net (code "36") (name "/en_jarka_7") (class "Default")
      (node (ref "DD5") (pin "6") (pinfunction "QG_6") (pintype "output"))
    )
    (net (code "39") (name "/en_jarka_dcdc") (class "Default")
      (node (ref "DD5") (pin "7") (pinfunction "QH_7") (pintype "output"))
    )
    (net (code "40") (name "/en_ox") (class "Default")
      (node (ref "DD6") (pin "2") (pinfunction "QC_2") (pintype "output"))
    )
    (net (code "41") (name "/en_sim") (class "Default")
      (node (ref "DA1") (pin "1") (pinfunction "INPUT_1") (pintype "passive"))
      (node (ref "DD6") (pin "4") (pinfunction "QE_4") (pintype "output"))
    )
    (net (code "42") (name "/en_vilka") (class "Default")
      (node (ref "DA2") (pin "1") (pinfunction "INPUT_1") (pintype "passive"))
      (node (ref "DD6") (pin "3") (pinfunction "QD_3") (pintype "output"))
    )
    (net (code "43") (name "/koncevik") (class "Default")
      (node (ref "DD4") (pin "9") (pinfunction "D6_9") (pintype "bidirectional"))
      (node (ref "R15") (pin "1") (pinfunction "1_1") (pintype "passive"))
      (node (ref "R20") (pin "1") (pinfunction "1_1") (pintype "passive"))
    )
    (net (code "44") (name "/latch") (class "Default")
      (node (ref "DD4") (pin "5") (pinfunction "D2_5") (pintype "bidirectional"))
      (node (ref "DD5") (pin "12") (pinfunction "LATCH_CLK_12") (pintype "input"))
      (node (ref "DD6") (pin "12") (pinfunction "LATCH_CLK_12") (pintype "input"))
    )
    (net (code "46") (name "/panel_1") (class "Default")
      (node (ref "XP1") (pin "B1") (pinfunction "B1_B1") (pintype "passive"))
      (node (ref "XP1") (pin "B2") (pinfunction "B2_B2") (pintype "passive"))
    )
    (net (code "47") (name "/panel_2") (class "Default")
      (node (ref "XP1") (pin "B3") (pinfunction "B3_B3") (pintype "passive"))
      (node (ref "XP1") (pin "B4") (pinfunction "B4_B4") (pintype "passive"))
    )
    (net (code "48") (name "/panel_3") (class "Default")
      (node (ref "XP1") (pin "B5") (pinfunction "B5_B5") (pintype "passive"))
      (node (ref "XP1") (pin "B6") (pinfunction "B6_B6") (pintype "passive"))
    )
    (net (code "49") (name "/panel_4") (class "Default")
      (node (ref "XP1") (pin "B7") (pinfunction "B7_B7") (pintype "passive"))
      (node (ref "XP1") (pin "B8") (pinfunction "B8_B8") (pintype "passive"))
    )
    (net (code "50") (name "/panel_5") (class "Default")
      (node (ref "XP1") (pin "B10") (pinfunction "B10_B10") (pintype "passive"))
      (node (ref "XP1") (pin "B9") (pinfunction "B9_B9") (pintype "passive"))
    )
    (net (code "51") (name "/panel_6") (class "Default")
      (node (ref "XP1") (pin "B11") (pinfunction "B11_B11") (pintype "passive"))
      (node (ref "XP1") (pin "B12") (pinfunction "B12_B12") (pintype "passive"))
    )
    (net (code "52") (name "/panel_7") (class "Default")
      (node (ref "XP1") (pin "B13") (pinfunction "B13_B13") (pintype "passive"))
      (node (ref "XP1") (pin "B14") (pinfunction "B14_B14") (pintype "passive"))
    )
    (net (code "55") (name "/reset") (class "Default")
      (node (ref "DD4") (pin "12") (pinfunction "D9_12") (pintype "bidirectional"))
      (node (ref "DD4") (pin "28") (pinfunction "RESET_28") (pintype "input"))
    )
    (net (code "57") (name "/voltage_1") (class "Default")
      (node (ref "DD7") (pin "13") (pinfunction "Y0_13") (pintype "passive"))
    )
    (net (code "58") (name "/voltage_2") (class "Default")
      (node (ref "DD7") (pin "14") (pinfunction "Y1_14") (pintype "passive"))
    )
    (net (code "59") (name "/voltage_3") (class "Default")
      (node (ref "DD7") (pin "15") (pinfunction "Y2_15") (pintype "passive"))
    )
    (net (code "60") (name "/voltage_4") (class "Default")
      (node (ref "DD7") (pin "12") (pinfunction "Y3_12") (pintype "passive"))
    )
    (net (code "61") (name "/voltage_5") (class "Default")
      (node (ref "DD7") (pin "1") (pinfunction "Y4_1") (pintype "passive"))
    )
    (net (code "62") (name "/voltage_6") (class "Default")
      (node (ref "DD7") (pin "2") (pinfunction "Y6_2") (pintype "passive"))
    )
    (net (code "63") (name "/voltage_7") (class "Default")
      (node (ref "DD7") (pin "5") (pinfunction "Y5_5") (pintype "passive"))
    )
    (net (code "66") (name "GND") (class "Default")
      (node (ref "C1") (pin "2") (pinfunction "2_2") (pintype "passive"))
      (node (ref "C10") (pin "1") (pinfunction "1_1") (pintype "passive"))
      (node (ref "C11") (pin "1") (pinfunction "1_1") (pintype "passive"))
      (node (ref "C12") (pin "1") (pinfunction "1_1") (pintype "passive"))
      (node (ref "C13") (pin "1") (pinfunction "1_1") (pintype "passive"))
      (node (ref "C2") (pin "1") (pinfunction "1_1") (pintype "passive"))
      (node (ref "C3") (pin "1") (pinfunction "1_1") (pintype "passive"))
      (node (ref "C4") (pin "2") (pinfunction "2_2") (pintype "passive"))
      (node (ref "C5") (pin "1") (pinfunction "1_1") (pintype "passive"))
      (node (ref "C6") (pin "1") (pinfunction "1_1") (pintype "passive"))
      (node (ref "C7") (pin "2") (pinfunction "2_2") (pintype "passive"))
      (node (ref "C8") (pin "2") (pinfunction "2_2") (pintype "passive"))
      (node (ref "C9") (pin "1") (pinfunction "1_1") (pintype "passive"))
      (node (ref "D1") (pin "3") (pinfunction "16_3") (pintype "passive"))
      (node (ref "D2") (pin "3") (pinfunction "16_3") (pintype "passive"))
      (node (ref "DA1") (pin "3") (pinfunction "GND_3") (pintype "passive"))
      (node (ref "DA2") (pin "3") (pinfunction "GND_3") (pintype "passive"))
      (node (ref "DD1") (pin "5") (pinfunction "GND_5") (pintype "passive"))
      (node (ref "DD2") (pin "2") (pinfunction "GND1_2") (pintype "passive"))
      (node (ref "DD2") (pin "9") (pinfunction "GND2_9") (pintype "passive"))
      (node (ref "DD3") (pin "2") (pinfunction "GND_2") (pintype "passive"))
      (node (ref "DD3") (pin "6") (pinfunction "GND_6") (pintype "passive"))
      (node (ref "DD4") (pin "29") (pinfunction "COM/GND_29") (pintype "power_in"))
      (node (ref "DD4") (pin "4") (pinfunction "COM/GND_4") (pintype "power_in"))
      (node (ref "DD5") (pin "13") (pinfunction "~{OE}_13") (pintype "input"))
      (node (ref "DD5") (pin "8") (pinfunction "GND_8") (pintype "power_in"))
      (node (ref "DD6") (pin "13") (pinfunction "~{OE}_13") (pintype "input"))
      (node (ref "DD6") (pin "8") (pinfunction "GND_8") (pintype "power_in"))
      (node (ref "DD7") (pin "6") (pinfunction "~{E}_6") (pintype "passive"))
      (node (ref "DD7") (pin "8") (pinfunction "GND_8") (pintype "passive"))
      (node (ref "DD8") (pin "GND") (pinfunction "GND_GND") (pintype "power_in"))
      (node (ref "R10") (pin "1") (pinfunction "1_1") (pintype "passive"))
      (node (ref "R13") (pin "1") (pinfunction "1_1") (pintype "passive"))
      (node (ref "R14") (pin "1") (pinfunction "1_1") (pintype "passive"))
      (node (ref "R3") (pin "1") (pinfunction "1_1") (pintype "passive"))
      (node (ref "R4") (pin "1") (pinfunction "1_1") (pintype "passive"))
      (node (ref "R6") (pin "1") (pinfunction "1_1") (pintype "passive"))
      (node (ref "R8") (pin "1") (pinfunction "1_1") (pintype "passive"))
      (node (ref "R9") (pin "1") (pinfunction "1_1") (pintype "passive"))
      (node (ref "U1") (pin "3") (pinfunction "3_3") (pintype "passive"))
      (node (ref "VD1") (pin "1") (pinfunction "1_1") (pintype "passive"))
      (node (ref "VD10") (pin "1") (pinfunction "1_1") (pintype "passive"))
      (node (ref "VD11") (pin "1") (pinfunction "1_1") (pintype "passive"))
      (node (ref "VD2") (pin "1") (pinfunction "1_1") (pintype "passive"))
      (node (ref "VD3") (pin "1") (pinfunction "1_1") (pintype "passive"))
      (node (ref "VD4") (pin "1") (pinfunction "1_1") (pintype "passive"))
      (node (ref "VD6") (pin "1") (pinfunction "1_1") (pintype "passive"))
      (node (ref "VD7") (pin "1") (pinfunction "1_1") (pintype "passive"))
      (node (ref "VD8") (pin "1") (pinfunction "1_1") (pintype "passive"))
      (node (ref "VD9") (pin "1") (pinfunction "1_1") (pintype "passive"))
      (node (ref "X1") (pin "N") (pinfunction "N_N") (pintype "passive"))
      (node (ref "XP1") (pin "A16") (pinfunction "A16_A16") (pintype "passive"))
      (node (ref "XP1") (pin "B15") (pinfunction "B15_B15") (pintype "passive"))
      (node (ref "XP1") (pin "B16") (pinfunction "B16_B16") (pintype "passive"))
    )
    (net (code "67") (name "Net-(DA1-MultiSense)") (class "Default")
      (node (ref "DA1") (pin "4") (pinfunction "MultiSense_4") (pintype "passive"))
      (node (ref "R4") (pin "2") (pinfunction "2_2") (pintype "passive"))
    )
    (net (code "68") (name "Net-(DA1-SEn)") (class "Default")
      (node (ref "DA1") (pin "2") (pinfunction "SEn_2") (pintype "passive"))
      (node (ref "R3") (pin "2") (pinfunction "2_2") (pintype "passive"))
    )
    (net (code "69") (name "Net-(DA2-MultiSense)") (class "Default")
      (node (ref "DA2") (pin "4") (pinfunction "MultiSense_4") (pintype "passive"))
      (node (ref "R9") (pin "2") (pinfunction "2_2") (pintype "passive"))
    )
    (net (code "70") (name "Net-(DA2-SEn)") (class "Default")
      (node (ref "DA2") (pin "2") (pinfunction "SEn_2") (pintype "passive"))
      (node (ref "R8") (pin "2") (pinfunction "2_2") (pintype "passive"))
    )
    (net (code "71") (name "Net-(DD1-DE)") (class "Default")
      (node (ref "DD1") (pin "2") (pinfunction "RE_2") (pintype "passive"))
      (node (ref "DD1") (pin "3") (pinfunction "DE_3") (pintype "passive"))
      (node (ref "SB2") (pin "1") (pinfunction "1_1") (pintype "passive"))
    )
    (net (code "72") (name "Net-(DD1-DI)") (class "Default")
      (node (ref "DD1") (pin "4") (pinfunction "DI_4") (pintype "passive"))
      (node (ref "SB3") (pin "1") (pinfunction "1_1") (pintype "passive"))
    )
    (net (code "73") (name "Net-(DD1-RO)") (class "Default")
      (node (ref "DD1") (pin "1") (pinfunction "RO_1") (pintype "passive"))
      (node (ref "SB1") (pin "1") (pinfunction "1_1") (pintype "passive"))
    )
    (net (code "74") (name "Net-(DD2-DE)") (class "Default")
      (node (ref "DD2") (pin "4") (pinfunction "~{RE}_4") (pintype "passive"))
      (node (ref "DD2") (pin "5") (pinfunction "DE_5") (pintype "passive"))
      (node (ref "DD4") (pin "7") (pinfunction "D4_7") (pintype "bidirectional"))
    )
    (net (code "75") (name "Net-(DD2-RX)") (class "Default")
      (node (ref "DD2") (pin "3") (pinfunction "RX_3") (pintype "passive"))
      (node (ref "DD4") (pin "6") (pinfunction "D3_6") (pintype "bidirectional"))
    )
    (net (code "76") (name "Net-(DD2-TX)") (class "Default")
      (node (ref "DD2") (pin "6") (pinfunction "TX_6") (pintype "passive"))
      (node (ref "DD4") (pin "8") (pinfunction "D5_8") (pintype "bidirectional"))
    )
    (net (code "77") (name "Net-(DD3-rx)") (class "Default")
      (node (ref "DD3") (pin "3") (pinfunction "rx_3") (pintype "passive"))
      (node (ref "DD4") (pin "2") (pinfunction "D0/RX_2") (pintype "bidirectional"))
    )
    (net (code "78") (name "Net-(DD3-tx)") (class "Default")
      (node (ref "DD3") (pin "4") (pinfunction "tx_4") (pintype "passive"))
      (node (ref "DD4") (pin "1") (pinfunction "D1/TX_1") (pintype "bidirectional"))
    )
    (net (code "79") (name "Net-(DD4-A5)") (class "Default")
      (node (ref "DD4") (pin "24") (pinfunction "A5_24") (pintype "input"))
      (node (ref "SB1") (pin "2") (pinfunction "2_2") (pintype "passive"))
    )
    (net (code "80") (name "Net-(DD4-A6)") (class "Default")
      (node (ref "DD4") (pin "25") (pinfunction "A6_25") (pintype "input"))
      (node (ref "SB2") (pin "2") (pinfunction "2_2") (pintype "passive"))
    )
    (net (code "81") (name "Net-(DD4-A7)") (class "Default")
      (node (ref "DD4") (pin "26") (pinfunction "A7_26") (pintype "input"))
      (node (ref "SB3") (pin "2") (pinfunction "2_2") (pintype "passive"))
    )
    (net (code "82") (name "Net-(DD4-D7)") (class "Default")
      (node (ref "DD4") (pin "10") (pinfunction "D7_10") (pintype "bidirectional"))
      (node (ref "DD5") (pin "14") (pinfunction "A_14") (pintype "input"))
    )
    (net (code "83") (name "Net-(DD4-D10)") (class "Default")
      (node (ref "DD4") (pin "13") (pinfunction "D10_13") (pintype "bidirectional"))
      (node (ref "DD5") (pin "11") (pinfunction "SHIFT_CLK_11") (pintype "input"))
      (node (ref "DD6") (pin "11") (pinfunction "SHIFT_CLK_11") (pintype "input"))
    )
    (net (code "84") (name "Net-(DD4-D11{slash}MOSI)") (class "Default")
      (node (ref "DD4") (pin "14") (pinfunction "D11/MOSI_14") (pintype "bidirectional"))
      (node (ref "DD7") (pin "11") (pinfunction "S0_11") (pintype "passive"))
    )
    (net (code "85") (name "Net-(DD4-D12{slash}MISO)") (class "Default")
      (node (ref "DD4") (pin "15") (pinfunction "D12/MISO_15") (pintype "bidirectional"))
      (node (ref "DD7") (pin "10") (pinfunction "S1_10") (pintype "passive"))
    )
    (net (code "86") (name "Net-(DD4-D13{slash}SCK)") (class "Default")
      (node (ref "DD4") (pin "16") (pinfunction "D13/SCK_16") (pintype "bidirectional"))
      (node (ref "DD7") (pin "9") (pinfunction "S2_9") (pintype "passive"))
    )
    (net (code "87") (name "Net-(DD5-SQH)") (class "Default")
      (node (ref "DD5") (pin "9") (pinfunction "SQH_9") (pintype "output"))
      (node (ref "DD6") (pin "14") (pinfunction "A_14") (pintype "input"))
    )
    (net (code "88") (name "Net-(DD7-Y7)") (class "Default")
      (node (ref "C12") (pin "2") (pinfunction "2_2") (pintype "passive"))
      (node (ref "DD7") (pin "4") (pinfunction "Y7_4") (pintype "passive"))
      (node (ref "R12") (pin "1") (pinfunction "1_1") (pintype "passive"))
      (node (ref "R13") (pin "2") (pinfunction "2_2") (pintype "passive"))
    )
    (net (code "89") (name "Net-(F1-Pad1)") (class "Default")
      (node (ref "F1") (pin "1") (pinfunction "1_1") (pintype "passive"))
      (node (ref "X1") (pin "P") (pinfunction "P_P") (pintype "passive"))
    )
    (net (code "90") (name "Net-(R5-Pad1)") (class "Default")
      (node (ref "R5") (pin "1") (pinfunction "1_1") (pintype "passive"))
      (node (ref "R6") (pin "2") (pinfunction "2_2") (pintype "passive"))
      (node (ref "U1") (pin "1") (pinfunction "1_1") (pintype "passive"))
    )
    (net (code "91") (name "Net-(R10-Pad2)") (class "Default")
      (node (ref "R10") (pin "2") (pinfunction "2_2") (pintype "passive"))
      (node (ref "VD5") (pin "1") (pinfunction "1_1") (pintype "passive"))
      (node (ref "VT1") (pin "1") (pinfunction "1_1") (pintype "passive"))
    )
    (net (code "92") (name "Net-(R11-Pad1)") (class "Default")
      (node (ref "R11") (pin "1") (pinfunction "1_1") (pintype "passive"))
      (node (ref "VT1") (pin "2") (pinfunction "2_2") (pintype "passive"))
    )
    (net (code "93") (name "Net-(R20-Pad2)") (class "Default")
      (node (ref "R20") (pin "2") (pinfunction "2_2") (pintype "passive"))
      (node (ref "XP1") (pin "A8") (pinfunction "A8_A8") (pintype "passive"))
    )
    (net (code "94") (name "Net-(R21-Pad2)") (class "Default")
      (node (ref "R21") (pin "2") (pinfunction "2_2") (pintype "passive"))
      (node (ref "XP1") (pin "A10") (pinfunction "A10_A10") (pintype "passive"))
    )
    (net (code "95") (name "Net-(R22-Pad2)") (class "Default")
      (node (ref "R22") (pin "2") (pinfunction "2_2") (pintype "passive"))
      (node (ref "XP1") (pin "A11") (pinfunction "A11_A11") (pintype "passive"))
    )
    (net (code "96") (name "Net-(R23-Pad2)") (class "Default")
      (node (ref "R23") (pin "2") (pinfunction "2_2") (pintype "passive"))
      (node (ref "XP1") (pin "A12") (pinfunction "A12_A12") (pintype "passive"))
    )
    (net (code "97") (name "Net-(R24-Pad2)") (class "Default")
      (node (ref "R24") (pin "2") (pinfunction "2_2") (pintype "passive"))
      (node (ref "XP1") (pin "A13") (pinfunction "A13_A13") (pintype "passive"))
    )
    (net (code "98") (name "Net-(R25-Pad2)") (class "Default")
      (node (ref "R25") (pin "2") (pinfunction "2_2") (pintype "passive"))
      (node (ref "XP1") (pin "A14") (pinfunction "A14_A14") (pintype "passive"))
    )
    (net (code "99") (name "Net-(R26-Pad2)") (class "Default")
      (node (ref "R26") (pin "2") (pinfunction "2_2") (pintype "passive"))
      (node (ref "XP1") (pin "A15") (pinfunction "A15_A15") (pintype "passive"))
    )
    (net (code "100") (name "unconnected-(DD3-RST-Pad1)") (class "Default")
      (node (ref "DD3") (pin "1") (pinfunction "RST_1") (pintype "passive+no_connect"))
    )
    (net (code "101") (name "unconnected-(DD3-VDD-Pad5)") (class "Default")
      (node (ref "DD3") (pin "5") (pinfunction "VDD_5") (pintype "passive+no_connect"))
    )
    (net (code "102") (name "unconnected-(DD4-AREF-Pad18)") (class "Default")
      (node (ref "DD4") (pin "18") (pinfunction "AREF_18") (pintype "power_in"))
    )
    (net (code "103") (name "unconnected-(DD4-RESET-Pad3)") (class "Default")
      (node (ref "DD4") (pin "3") (pinfunction "RESET_3") (pintype "input+no_connect"))
    )
    (net (code "104") (name "unconnected-(DD4-VIN-Pad30)") (class "Default")
      (node (ref "DD4") (pin "30") (pinfunction "VIN_30") (pintype "input+no_connect"))
    )
    (net (code "105") (name "unconnected-(DD6-QF-Pad5)") (class "Default")
      (node (ref "DD6") (pin "5") (pinfunction "QF_5") (pintype "output+no_connect"))
    )
    (net (code "106") (name "unconnected-(DD6-QG-Pad6)") (class "Default")
      (node (ref "DD6") (pin "6") (pinfunction "QG_6") (pintype "output+no_connect"))
    )
    (net (code "107") (name "unconnected-(DD6-QH-Pad7)") (class "Default")
      (node (ref "DD6") (pin "7") (pinfunction "QH_7") (pintype "output+no_connect"))
    )
    (net (code "108") (name "unconnected-(DD6-SQH-Pad9)") (class "Default")
      (node (ref "DD6") (pin "9") (pinfunction "SQH_9") (pintype "output+no_connect"))
    )
    (net (code "109") (name "unconnected-(DD8-NULL-PadNC)") (class "Default")
      (node (ref "DD8") (pin "NC") (pinfunction "NULL_NC") (pintype "passive"))
    )
  )
)
